# TVI-Kbd-converter.net
KiCad netlist of a schematic drawn in EAGLE
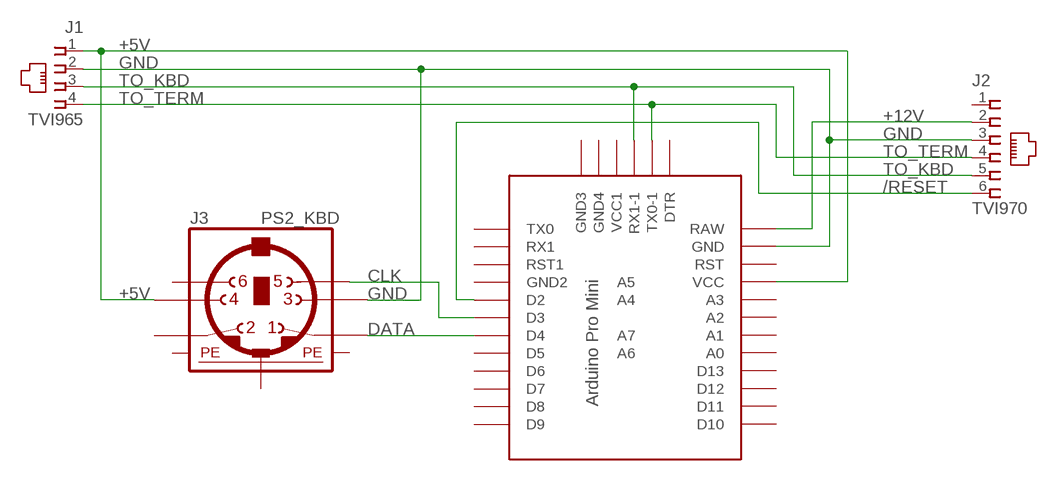
[diagram p0: schematic, sheet 1]

(export (version "E")
  (design (tool "Eeschema 10.0.6"))
  (components
    (comp (ref "J1")
      (value "TVI965")
      (footprint "eagle-import:215875-3")
      (libsource (lib "eagle-import") (part "215875-3"))
    )
    (comp (ref "J2")
      (value "TVI970")
      (footprint "eagle-import:555165-1")
      (libsource (lib "eagle-import") (part "555165-1"))
    )
    (comp (ref "J3")
      (value "PS2_KBD")
      (footprint "eagle-import:M_DIN6")
      (libsource (lib "eagle-import") (part "MINI_DIN_6"))
    )
    (comp (ref "U$1")
      (value "PRO-MINI-2")
      (footprint "eagle-import:PRO-MINI-2")
      (libsource (lib "eagle-import") (part "PRO-MINI-2"))
    )
  )
  (nets
    (net (code "1") (name "/+5V") (class "Default")
      (node (ref "J1") (pin "1") (pinfunction "1_1") (pintype "passive"))
      (node (ref "J3") (pin "5") (pinfunction "5_5") (pintype "passive"))
      (node (ref "U$1") (pin "VCC") (pinfunction "VCC_VCC") (pintype "bidirectional"))
    )
    (net (code "2") (name "/+12V") (class "Default")
      (node (ref "J2") (pin "2") (pinfunction "2_2") (pintype "passive"))
      (node (ref "U$1") (pin "RAW") (pinfunction "RAW_RAW") (pintype "bidirectional"))
    )
    (net (code "3") (name "/CLK") (class "Default")
      (node (ref "J3") (pin "6") (pinfunction "6_6") (pintype "passive"))
      (node (ref "U$1") (pin "D3") (pinfunction "D3_D3") (pintype "bidirectional"))
    )
    (net (code "4") (name "/DATA") (class "Default")
      (node (ref "J3") (pin "1") (pinfunction "1_1") (pintype "passive"))
      (node (ref "U$1") (pin "D4") (pinfunction "D4_D4") (pintype "bidirectional"))
    )
    (net (code "5") (name "/GND") (class "Default")
      (node (ref "J1") (pin "2") (pinfunction "2_2") (pintype "passive"))
      (node (ref "J2") (pin "3") (pinfunction "3_3") (pintype "passive"))
      (node (ref "J3") (pin "3") (pinfunction "3_3") (pintype "passive"))
      (node (ref "U$1") (pin "GND") (pinfunction "GND_GND") (pintype "bidirectional"))
    )
    (net (code "6") (name "/PE1") (class "Default")
      (node (ref "J3") (pin "SH1") (pinfunction "PE1_SH1") (pintype "power_in"))
    )
    (net (code "7") (name "/PE2") (class "Default")
      (node (ref "J3") (pin "SH2") (pinfunction "PE2_SH2") (pintype "power_in"))
    )
    (net (code "8") (name "/PE3") (class "Default")
      (node (ref "J3") (pin "SH3") (pinfunction "PE3_SH3") (pintype "power_in"))
    )
    (net (code "9") (name "/TO_KBD") (class "Default")
      (node (ref "J1") (pin "3") (pinfunction "3_3") (pintype "passive"))
      (node (ref "J2") (pin "5") (pinfunction "5_5") (pintype "passive"))
      (node (ref "U$1") (pin "RX1-1") (pinfunction "RX1-1_RX1-1") (pintype "bidirectional"))
    )
    (net (code "10") (name "/TO_TERM") (class "Default")
      (node (ref "J1") (pin "4") (pinfunction "4_4") (pintype "passive"))
      (node (ref "J2") (pin "4") (pinfunction "4_4") (pintype "passive"))
      (node (ref "U$1") (pin "TX0-1") (pinfunction "TX0-1_TX0-1") (pintype "bidirectional"))
    )
    (net (code "11") (name "/{slash}RESET") (class "Default")
      (node (ref "J2") (pin "6") (pinfunction "6_6") (pintype "passive"))
      (node (ref "U$1") (pin "D2") (pinfunction "D2_D2") (pintype "bidirectional"))
    )
    (net (code "12") (name "unconnected-(J2-Pad1)") (class "Default")
      (node (ref "J2") (pin "1") (pinfunction "1_1") (pintype "passive"))
    )
    (net (code "13") (name "unconnected-(J3-Pad2)") (class "Default")
      (node (ref "J3") (pin "2") (pinfunction "2_2") (pintype "passive"))
    )
    (net (code "14") (name "unconnected-(J3-Pad8)") (class "Default")
      (node (ref "J3") (pin "8") (pinfunction "8_8") (pintype "passive"))
    )
    (net (code "15") (name "unconnected-(U$1-GND2-PadGND1)") (class "Default")
      (node (ref "U$1") (pin "GND1") (pinfunction "GND2_GND1") (pintype "bidirectional"))
    )
    (net (code "16") (name "unconnected-(U$1-GND3-PadGND2)") (class "Default")
      (node (ref "U$1") (pin "GND2") (pinfunction "GND3_GND2") (pintype "bidirectional"))
    )
    (net (code "17") (name "unconnected-(U$1-GND4-PadGND3)") (class "Default")
      (node (ref "U$1") (pin "GND3") (pinfunction "GND4_GND3") (pintype "bidirectional"))
    )
    (net (code "18") (name "unconnected-(U$1-PadA0)") (class "Default")
      (node (ref "U$1") (pin "A0") (pinfunction "A0_A0") (pintype "bidirectional"))
    )
    (net (code "19") (name "unconnected-(U$1-PadA1)") (class "Default")
      (node (ref "U$1") (pin "A1") (pinfunction "A1_A1") (pintype "bidirectional"))
    )
    (net (code "20") (name "unconnected-(U$1-PadA2)") (class "Default")
      (node (ref "U$1") (pin "A2") (pinfunction "A2_A2") (pintype "bidirectional"))
    )
    (net (code "21") (name "unconnected-(U$1-PadA3)") (class "Default")
      (node (ref "U$1") (pin "A3") (pinfunction "A3_A3") (pintype "bidirectional"))
    )
    (net (code "22") (name "unconnected-(U$1-PadA4)") (class "Default")
      (node (ref "U$1") (pin "A4") (pinfunction "A4_A4") (pintype "bidirectional"))
    )
    (net (code "23") (name "unconnected-(U$1-PadA5)") (class "Default")
      (node (ref "U$1") (pin "A5") (pinfunction "A5_A5") (pintype "bidirectional"))
    )
    (net (code "24") (name "unconnected-(U$1-PadA6)") (class "Default")
      (node (ref "U$1") (pin "A6") (pinfunction "A6_A6") (pintype "bidirectional"))
    )
    (net (code "25") (name "unconnected-(U$1-PadA7)") (class "Default")
      (node (ref "U$1") (pin "A7") (pinfunction "A7_A7") (pintype "bidirectional"))
    )
    (net (code "26") (name "unconnected-(U$1-PadD5)") (class "Default")
      (node (ref "U$1") (pin "D5") (pinfunction "D5_D5") (pintype "bidirectional"))
    )
    (net (code "27") (name "unconnected-(U$1-PadD6)") (class "Default")
      (node (ref "U$1") (pin "D6") (pinfunction "D6_D6") (pintype "bidirectional"))
    )
    (net (code "28") (name "unconnected-(U$1-PadD7)") (class "Default")
      (node (ref "U$1") (pin "D7") (pinfunction "D7_D7") (pintype "bidirectional"))
    )
    (net (code "29") (name "unconnected-(U$1-PadD8)") (class "Default")
      (node (ref "U$1") (pin "D8") (pinfunction "D8_D8") (pintype "bidirectional"))
    )
    (net (code "30") (name "unconnected-(U$1-PadD9)") (class "Default")
      (node (ref "U$1") (pin "D9") (pinfunction "D9_D9") (pintype "bidirectional"))
    )
    (net (code "31") (name "unconnected-(U$1-PadD10)") (class "Default")
      (node (ref "U$1") (pin "D10") (pinfunction "D10_D10") (pintype "bidirectional"))
    )
    (net (code "32") (name "unconnected-(U$1-PadD11)") (class "Default")
      (node (ref "U$1") (pin "D11") (pinfunction "D11_D11") (pintype "bidirectional"))
    )
    (net (code "33") (name "unconnected-(U$1-PadD12)") (class "Default")
      (node (ref "U$1") (pin "D12") (pinfunction "D12_D12") (pintype "bidirectional"))
    )
    (net (code "34") (name "unconnected-(U$1-PadD13)") (class "Default")
      (node (ref "U$1") (pin "D13") (pinfunction "D13_D13") (pintype "bidirectional"))
    )
    (net (code "35") (name "unconnected-(U$1-PadDTR)") (class "Default")
      (node (ref "U$1") (pin "DTR") (pinfunction "DTR_DTR") (pintype "bidirectional"))
    )
    (net (code "36") (name "unconnected-(U$1-PadRST)") (class "Default")
      (node (ref "U$1") (pin "RST") (pinfunction "RST_RST") (pintype "bidirectional"))
    )
    (net (code "37") (name "unconnected-(U$1-PadRST1)") (class "Default")
      (node (ref "U$1") (pin "RST1") (pinfunction "RST1_RST1") (pintype "bidirectional"))
    )
    (net (code "38") (name "unconnected-(U$1-PadRX1)") (class "Default")
      (node (ref "U$1") (pin "RX1") (pinfunction "RX1_RX1") (pintype "bidirectional"))
    )
    (net (code "39") (name "unconnected-(U$1-PadTX0)") (class "Default")
      (node (ref "U$1") (pin "TX0") (pinfunction "TX0_TX0") (pintype "bidirectional"))
    )
    (net (code "40") (name "unconnected-(U$1-PadVCC1)") (class "Default")
      (node (ref "U$1") (pin "VCC1") (pinfunction "VCC1_VCC1") (pintype "bidirectional"))
    )
  )
)
